# Sheet.net
KiCad netlist of a schematic drawn in Altium Designer
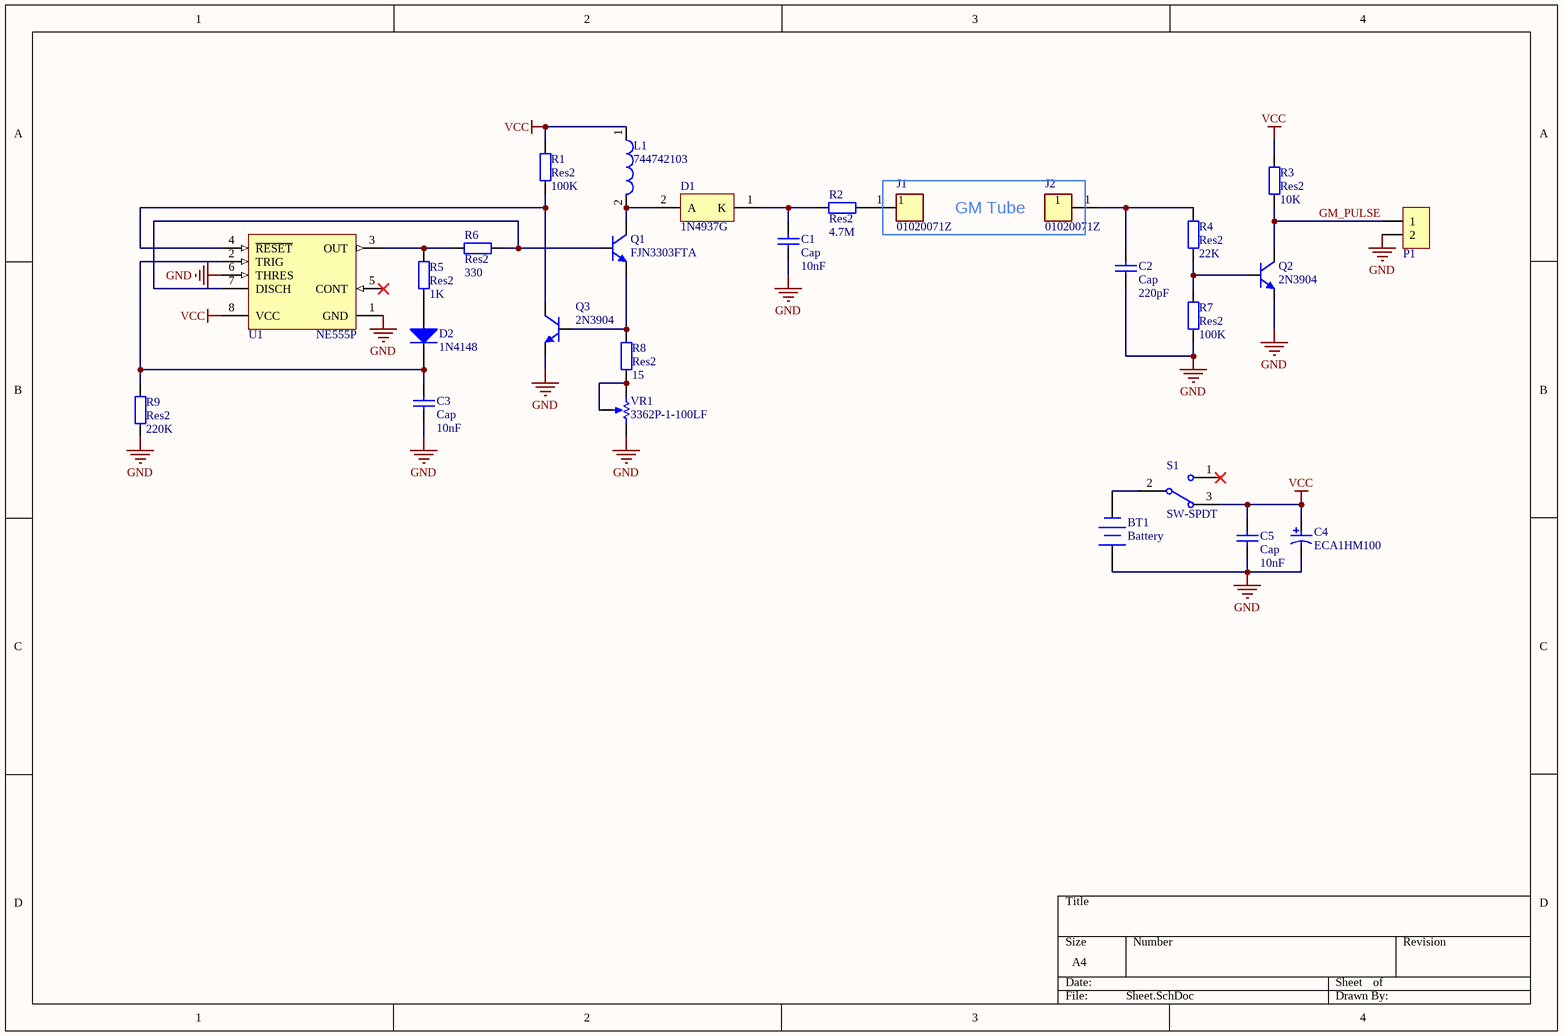
[diagram p0: Sheet.SchDoc]

(export (version "E")
  (design (tool "Eeschema 10.0.6"))
  (components
    (comp (ref "BT1")
      (value "Battery")
      (footprint "BAT-2")
      (description "Multicell Battery")
      (fields (field (name "PUBLISHER") "Altium Limited"))
      (libsource (lib "Miscellaneous Devices") (part "Battery"))
    )
    (comp (ref "C1")
      (value "Cap")
      (footprint "RAD-0.2")
      (description "Capacitor")
      (fields (field (name "ALTIUM_VALUE") "10nF") (field (name "PUBLISHER") "Altium Limited"))
      (libsource (lib "Miscellaneous Devices") (part "Cap"))
    )
    (comp (ref "C2")
      (value "Cap")
      (footprint "RAD-0.2")
      (description "Capacitor")
      (fields (field (name "ALTIUM_VALUE") "220pF") (field (name "PUBLISHER") "Altium Limited"))
      (libsource (lib "Miscellaneous Devices") (part "Cap"))
    )
    (comp (ref "C3")
      (value "Cap")
      (footprint "RAD-0.2")
      (description "Capacitor")
      (fields (field (name "ALTIUM_VALUE") "10nF") (field (name "PUBLISHER") "Altium Limited"))
      (libsource (lib "Miscellaneous Devices") (part "Cap"))
    )
    (comp (ref "C4")
      (value "ECA1HM100")
      (footprint "CAPPR55-200-1100X500X1200")
      (description "Aluminum Electrolytic Capacitor, 10 uF, +/- 20%, 50 V, -40 to 85 degC, 2-Pin THD, RoHS, Bulk")
      (fields (field (name "MANUFACTURER") "Panasonic") (field (name "TOLERANCE") "20%"))
      (libsource (lib "Altium Content Vault") (part "CAP-P-2"))
    )
    (comp (ref "C5")
      (value "Cap")
      (footprint "RAD-0.1")
      (description "Capacitor")
      (fields (field (name "ALTIUM_VALUE") "10nF") (field (name "PUBLISHER") "Altium Limited"))
      (libsource (lib "Miscellaneous Devices") (part "Cap"))
    )
    (comp (ref "D1")
      (value "1N4937G")
      (footprint "ONSC-AXIAL_LEAD-2-59-10_P")
      (description "Fast-Recovery Rectifier, 2-Pin Axial_Lead, Pb-Free, Bulk Bag")
      (fields (field (name "MANUFACTURER") "On Semiconductor"))
      (libsource (lib "Altium Content Vault") (part "ONSC-D-K1A2-2_A"))
    )
    (comp (ref "D2")
      (value "1N4148")
      (footprint "NXP-SOD27-2_V")
      (description "High-speed Diode, 100 V, 450 mA, 2-Pin SOD27, RoHS")
      (fields (field (name "MANUFACTURER") "NXP Semiconductors"))
      (libsource (lib "Altium Content Vault") (part "NXP-A1K2-2"))
    )
    (comp (ref "J1")
      (value "01020071Z")
      (footprint "FP-102-MFG")
      (description "FUSE CLIP CARTRIDGE 250V 15A PCB")
      (fields
        (field (name "MANUFACTURER") "Littelfuse Inc")
        (field (name "OCTOPART") "https://octopart.com/01020071z-littelfuse-18837869")
      )
      (libsource (lib "") (part "600373309f0643ccfefc365bd0e8f7b_1"))
    )
    (comp (ref "J2")
      (value "01020071Z")
      (footprint "FP-102-MFG")
      (description "FUSE CLIP CARTRIDGE 250V 15A PCB")
      (fields
        (field (name "MANUFACTURER") "Littelfuse Inc")
        (field (name "OCTOPART") "https://octopart.com/01020071z-littelfuse-18837869")
      )
      (libsource (lib "Altium Content Vault") (part "600373309f0643ccfefc365bd0e8f7b"))
    )
    (comp (ref "L1")
      (value "744742103")
      (footprint "WE-TI-L")
      (description "Radial Leaded Wire Wound Inductor WE-TI, L=10000 µH")
      (fields (field (name "MANUFACTURER") "Wuerth Elektronik"))
      (libsource (lib "Altium Content Vault") (part "PAS-IND-INDUCTOR-2"))
    )
    (comp (ref "P1")
      (value "HDR-1X2")
      (footprint "XH2.54-2P_H")
      (description "2P接插件")
      (fields (field (name "版权归属") "源创客"))
      (libsource (lib "接插件") (part "Header 2"))
    )
    (comp (ref "Q1")
      (value "FJN3303FTA")
      (footprint "TO92B")
      (description "高频放大-NPN型")
      (fields (field (name "版权归属") "源创客"))
      (libsource (lib "三极管") (part "8050-DIP"))
    )
    (comp (ref "Q2")
      (value "2N3904")
      (footprint "TO92B")
      (description "高频放大-NPN型")
      (fields (field (name "版权归属") "源创客"))
      (libsource (lib "三极管") (part "8050-DIP"))
    )
    (comp (ref "Q3")
      (value "2N3904")
      (footprint "TO92B")
      (description "高频放大-NPN型")
      (fields (field (name "版权归属") "源创客"))
      (libsource (lib "三极管") (part "8050-DIP"))
    )
    (comp (ref "R1")
      (value "Res2")
      (footprint "AXIAL-0.4")
      (description "Resistor")
      (fields (field (name "ALTIUM_VALUE") "100K") (field (name "PUBLISHER") "Altium Limited"))
      (libsource (lib "Miscellaneous Devices") (part "Res2"))
    )
    (comp (ref "R2")
      (value "Res2")
      (footprint "AXIAL-0.4")
      (description "Resistor")
      (fields (field (name "ALTIUM_VALUE") "4.7M") (field (name "PUBLISHER") "Altium Limited"))
      (libsource (lib "") (part "Res2_2"))
    )
    (comp (ref "R3")
      (value "Res2")
      (footprint "AXIAL-0.4")
      (description "Resistor")
      (fields (field (name "ALTIUM_VALUE") "10K") (field (name "PUBLISHER") "Altium Limited"))
      (libsource (lib "Miscellaneous Devices") (part "Res2"))
    )
    (comp (ref "R4")
      (value "Res2")
      (footprint "AXIAL-0.4")
      (description "Resistor")
      (fields (field (name "ALTIUM_VALUE") "22K") (field (name "PUBLISHER") "Altium Limited"))
      (libsource (lib "Miscellaneous Devices") (part "Res2"))
    )
    (comp (ref "R5")
      (value "Res2")
      (footprint "AXIAL-0.4")
      (description "Resistor")
      (fields (field (name "ALTIUM_VALUE") "1K") (field (name "PUBLISHER") "Altium Limited"))
      (libsource (lib "Miscellaneous Devices") (part "Res2"))
    )
    (comp (ref "R6")
      (value "Res2")
      (footprint "AXIAL-0.4")
      (description "Resistor")
      (fields (field (name "ALTIUM_VALUE") "330") (field (name "PUBLISHER") "Altium Limited"))
      (libsource (lib "") (part "Res2_1"))
    )
    (comp (ref "R7")
      (value "Res2")
      (footprint "AXIAL-0.4")
      (description "Resistor")
      (fields (field (name "ALTIUM_VALUE") "100K") (field (name "PUBLISHER") "Altium Limited"))
      (libsource (lib "Miscellaneous Devices") (part "Res2"))
    )
    (comp (ref "R8")
      (value "Res2")
      (footprint "AXIAL-0.4")
      (description "Resistor")
      (fields (field (name "ALTIUM_VALUE") "15") (field (name "PUBLISHER") "Altium Limited"))
      (libsource (lib "Miscellaneous Devices") (part "Res2"))
    )
    (comp (ref "R9")
      (value "Res2")
      (footprint "AXIAL-0.4")
      (description "Resistor")
      (fields (field (name "ALTIUM_VALUE") "220K") (field (name "PUBLISHER") "Altium Limited"))
      (libsource (lib "Miscellaneous Devices") (part "Res2"))
    )
    (comp (ref "S1")
      (value "SW-SPDT")
      (footprint "SW-TH_SK12D07VG4")
      (description "SPDT Subminiature Toggle Switch, Right Angle Mounting, Vertical Actuation")
      (fields (field (name "PUBLISHER") "Altium Limited"))
      (libsource (lib "Miscellaneous Devices") (part "SW-SPDT"))
    )
    (comp (ref "U1")
      (value "NE555P")
      (footprint "P0008A")
      (description "Precision Timer, 4.5 to 16 V, 0 to 70 degC, 8-Pin DIP, Pb-Free, Tube")
      (fields (field (name "MANUFACTURER") "TexasInstruments"))
      (libsource (lib "Altium Content Vault") (part "TI-NE555-P8"))
    )
    (comp (ref "VR1")
      (value "3362P-1-100LF")
      (footprint "BOUR-3362P")
      (fields (field (name "TOLERANCE") "1%"))
      (libsource (lib "Altium Content Vault") (part "RES-POT-3"))
    )
  )
  (nets
    (net (code "1") (name "/GM_PULSE") (class "Default")
      (node (ref "P1") (pin "1") (pinfunction "1_1") (pintype "passive"))
      (node (ref "Q2") (pin "3") (pinfunction "C_3") (pintype "passive"))
      (node (ref "R3") (pin "1") (pinfunction "1_1") (pintype "passive"))
    )
    (net (code "2") (name "GND") (class "Default")
      (node (ref "BT1") (pin "1") (pinfunction "+_1") (pintype "passive"))
      (node (ref "C1") (pin "1") (pinfunction "1_1") (pintype "passive"))
      (node (ref "C2") (pin "1") (pinfunction "1_1") (pintype "passive"))
      (node (ref "C3") (pin "1") (pinfunction "1_1") (pintype "passive"))
      (node (ref "C4") (pin "2") (pinfunction "2_2") (pintype "passive"))
      (node (ref "C5") (pin "1") (pinfunction "1_1") (pintype "passive"))
      (node (ref "P1") (pin "2") (pinfunction "2_2") (pintype "passive"))
      (node (ref "Q2") (pin "1") (pinfunction "E_1") (pintype "passive"))
      (node (ref "Q3") (pin "1") (pinfunction "E_1") (pintype "passive"))
      (node (ref "R7") (pin "1") (pinfunction "1_1") (pintype "passive"))
      (node (ref "R9") (pin "1") (pinfunction "1_1") (pintype "passive"))
      (node (ref "U1") (pin "1") (pinfunction "GND_1") (pintype "power_in"))
      (node (ref "U1") (pin "6") (pinfunction "THRES_6") (pintype "input"))
      (node (ref "VR1") (pin "3") (pinfunction "CW_3") (pintype "passive"))
    )
    (net (code "3") (name "Net-(BT1--)") (class "Default")
      (node (ref "BT1") (pin "2") (pinfunction "-_2") (pintype "passive"))
      (node (ref "S1") (pin "2") (pinfunction "2_2") (pintype "passive"))
    )
    (net (code "4") (name "Net-(C2-Pad2)") (class "Default")
      (node (ref "C2") (pin "2") (pinfunction "2_2") (pintype "passive"))
      (node (ref "J2") (pin "1") (pinfunction "1_1") (pintype "passive"))
      (node (ref "R4") (pin "2") (pinfunction "2_2") (pintype "passive"))
    )
    (net (code "5") (name "Net-(D1-A)") (class "Default")
      (node (ref "D1") (pin "2") (pinfunction "A_2") (pintype "passive"))
      (node (ref "L1") (pin "2") (pinfunction "2_2") (pintype "passive"))
      (node (ref "Q1") (pin "3") (pinfunction "C_3") (pintype "passive"))
    )
    (net (code "6") (name "Net-(D1-K)") (class "Default")
      (node (ref "C1") (pin "2") (pinfunction "2_2") (pintype "passive"))
      (node (ref "D1") (pin "1") (pinfunction "K_1") (pintype "passive"))
      (node (ref "R2") (pin "2") (pinfunction "2_2") (pintype "passive"))
    )
    (net (code "7") (name "Net-(D2-A)") (class "Default")
      (node (ref "D2") (pin "1") (pinfunction "A_1") (pintype "passive"))
      (node (ref "R5") (pin "1") (pinfunction "1_1") (pintype "passive"))
    )
    (net (code "8") (name "Net-(D2-K)") (class "Default")
      (node (ref "C3") (pin "2") (pinfunction "2_2") (pintype "passive"))
      (node (ref "D2") (pin "2") (pinfunction "K_2") (pintype "passive"))
      (node (ref "R9") (pin "2") (pinfunction "2_2") (pintype "passive"))
      (node (ref "U1") (pin "2") (pinfunction "TRIG_2") (pintype "input"))
    )
    (net (code "9") (name "Net-(J1-Pad1)") (class "Default")
      (node (ref "J1") (pin "1") (pinfunction "1_1") (pintype "passive"))
      (node (ref "R2") (pin "1") (pinfunction "1_1") (pintype "passive"))
    )
    (net (code "10") (name "Net-(Q1-B)") (class "Default")
      (node (ref "Q1") (pin "2") (pinfunction "B_2") (pintype "passive"))
      (node (ref "R6") (pin "2") (pinfunction "2_2") (pintype "passive"))
      (node (ref "U1") (pin "7") (pinfunction "DISCH_7") (pintype "open_collector"))
    )
    (net (code "11") (name "Net-(Q1-E)") (class "Default")
      (node (ref "Q1") (pin "1") (pinfunction "E_1") (pintype "passive"))
      (node (ref "Q3") (pin "2") (pinfunction "B_2") (pintype "passive"))
      (node (ref "R8") (pin "2") (pinfunction "2_2") (pintype "passive"))
    )
    (net (code "12") (name "Net-(Q2-B)") (class "Default")
      (node (ref "Q2") (pin "2") (pinfunction "B_2") (pintype "passive"))
      (node (ref "R4") (pin "1") (pinfunction "1_1") (pintype "passive"))
      (node (ref "R7") (pin "2") (pinfunction "2_2") (pintype "passive"))
    )
    (net (code "13") (name "Net-(Q3-C)") (class "Default")
      (node (ref "Q3") (pin "3") (pinfunction "C_3") (pintype "passive"))
      (node (ref "R1") (pin "1") (pinfunction "1_1") (pintype "passive"))
      (node (ref "U1") (pin "4") (pinfunction "~{RESET}_4") (pintype "input"))
    )
    (net (code "14") (name "Net-(U1-OUT)") (class "Default")
      (node (ref "R5") (pin "2") (pinfunction "2_2") (pintype "passive"))
      (node (ref "R6") (pin "1") (pinfunction "1_1") (pintype "passive"))
      (node (ref "U1") (pin "3") (pinfunction "OUT_3") (pintype "output"))
    )
    (net (code "15") (name "Net-(VR1-CCW)") (class "Default")
      (node (ref "R8") (pin "1") (pinfunction "1_1") (pintype "passive"))
      (node (ref "VR1") (pin "1") (pinfunction "CCW_1") (pintype "passive"))
      (node (ref "VR1") (pin "2") (pinfunction "S_2") (pintype "passive"))
    )
    (net (code "16") (name "VCC") (class "Default")
      (node (ref "C4") (pin "1") (pinfunction "1_1") (pintype "passive"))
      (node (ref "C5") (pin "2") (pinfunction "2_2") (pintype "passive"))
      (node (ref "L1") (pin "1") (pinfunction "1_1") (pintype "passive"))
      (node (ref "R1") (pin "2") (pinfunction "2_2") (pintype "passive"))
      (node (ref "R3") (pin "2") (pinfunction "2_2") (pintype "passive"))
      (node (ref "S1") (pin "3") (pinfunction "3_3") (pintype "passive"))
      (node (ref "U1") (pin "8") (pinfunction "VCC_8") (pintype "power_in"))
    )
    (net (code "17") (name "unconnected-(S1-Pad1)") (class "Default")
      (node (ref "S1") (pin "1") (pinfunction "1_1") (pintype "passive+no_connect"))
    )
    (net (code "18") (name "unconnected-(U1-CONT-Pad5)") (class "Default")
      (node (ref "U1") (pin "5") (pinfunction "CONT_5") (pintype "input+no_connect"))
    )
  )
)
